# Car_Driver.net
KiCad netlist of a schematic drawn in Altium Designer
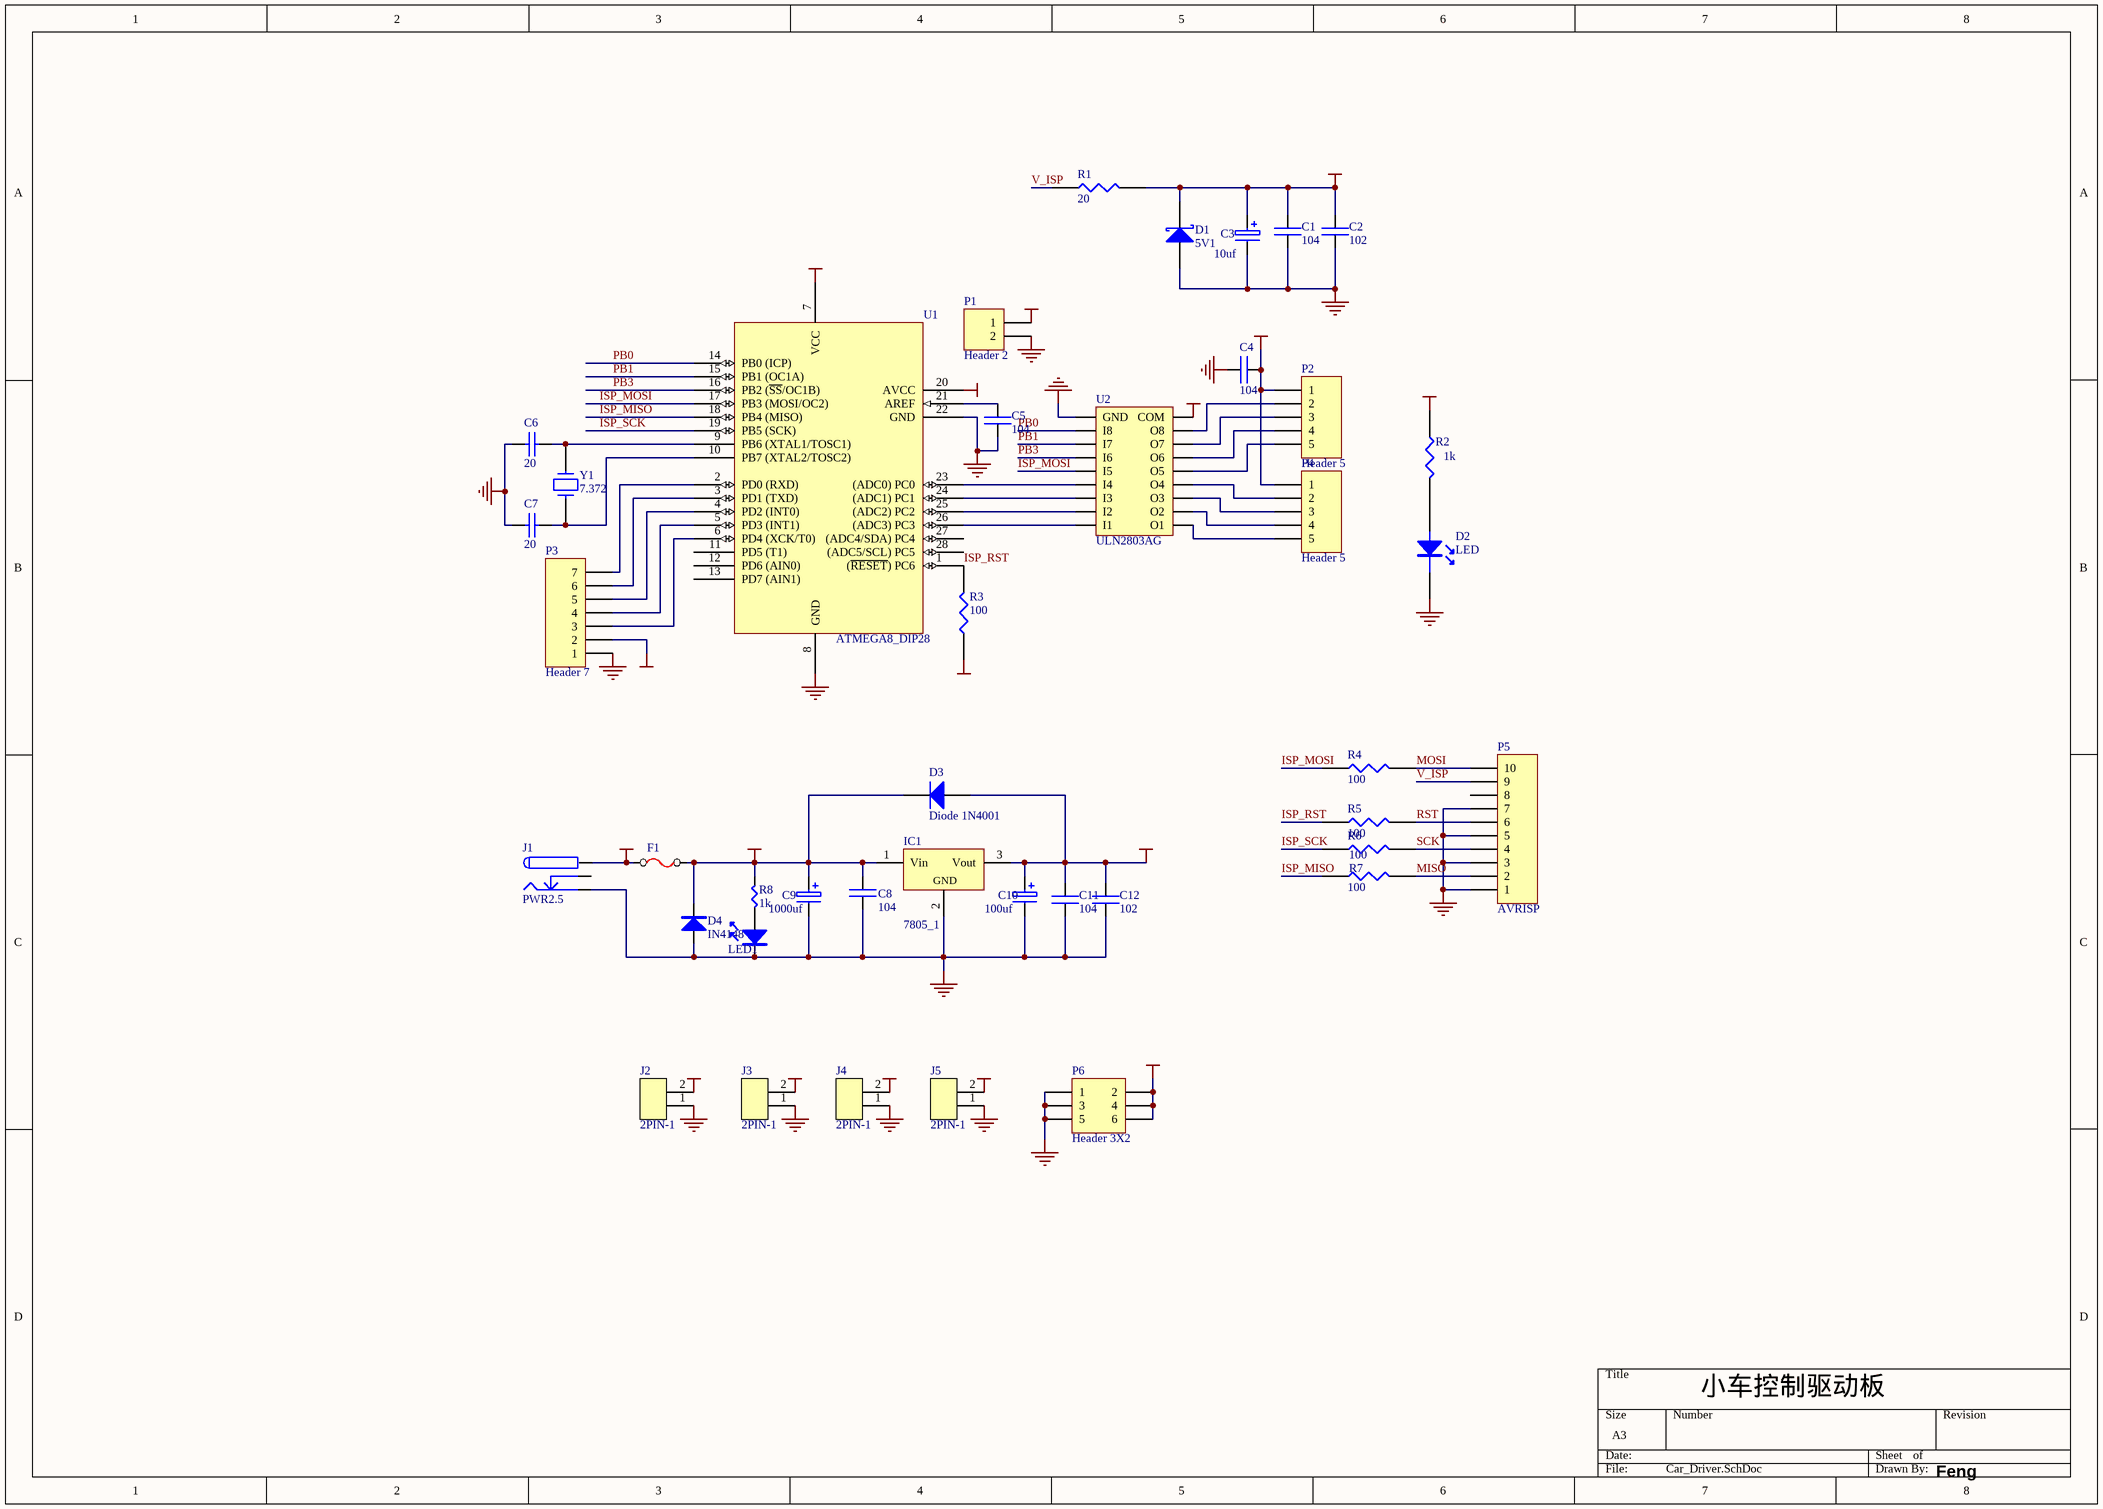
[diagram p0: Car_Driver.SchDoc]

(export (version "E")
  (design (tool "Eeschema 10.0.6"))
  (components
    (comp (ref "C1") (value "104") (footprint "CB1") (libsource (lib "Traffic_light") (part "E_4")))
    (comp (ref "C2") (value "102") (footprint "CB1") (libsource (lib "Traffic_light") (part "E_4")))
    (comp (ref "C3") (value "10uf") (footprint "10U16") (libsource (lib "Traffic_light") (part "E_2")))
    (comp (ref "C4") (value "104") (footprint "CB1") (libsource (lib "Traffic_light") (part "E_4")))
    (comp (ref "C5") (value "104") (footprint "CB1") (libsource (lib "Traffic_light") (part "E_4")))
    (comp (ref "C6")
      (value "20")
      (footprint "CB1")
      (description "Capacitor")
      (libsource (lib "*") (part "CAP"))
    )
    (comp (ref "C7")
      (value "20")
      (footprint "CB1")
      (description "Capacitor")
      (libsource (lib "*") (part "CAP"))
    )
    (comp (ref "C8") (value "104") (footprint "cap_104") (libsource (lib "*") (part "E_4")))
    (comp (ref "C9") (value "1000uf") (footprint "470U25") (libsource (lib "*") (part "E_2")))
    (comp (ref "C10") (value "100uf") (footprint "470U25") (libsource (lib "*") (part "E_2")))
    (comp (ref "C11") (value "104") (footprint "cap_104") (libsource (lib "*") (part "E_4")))
    (comp (ref "C12") (value "102") (footprint "C0.1/0.2") (libsource (lib "*") (part "E_4")))
    (comp (ref "D1")
      (value "5V1")
      (footprint "DIODE")
      (description "Schottky Diode")
      (fields (field (name "PUBLISHER") "Altium Limited"))
      (libsource (lib "Miscellaneous Devices") (part "D Schottky"))
    )
    (comp (ref "D2") (value "LED") (footprint "LED_5") (libsource (lib "*") (part "LED")))
    (comp (ref "D3")
      (value "Diode 1N4001")
      (footprint "diode")
      (description "1 Amp General Purpose Rectifier")
      (fields (field (name "PUBLISHER") "Altium Limited"))
      (libsource (lib "Miscellaneous Devices") (part "Diode 1N4001"))
    )
    (comp (ref "D4") (value "IN4148") (footprint "DIODE") (libsource (lib "晶体管") (part "IN4148")))
    (comp (ref "F1")
      (value "FUSE")
      (footprint "CAP_104")
      (description "Fuse")
      (libsource (lib "模拟器件") (part "FUSE"))
    )
    (comp (ref "IC1") (value "7805_1") (footprint "to-220") (libsource (lib "*") (part "7805_1")))
    (comp (ref "J1")
      (value "PWR2.5")
      (footprint "DC3")
      (description "Low Voltage Power Supply Connector")
      (fields (field (name "PUBLISHER") "Altium Limited"))
      (libsource (lib "Traffic_light") (part "PWR2.5"))
    )
    (comp (ref "J2") (value "2PIN-1") (footprint "HDR1X2H") (libsource (lib "接插件") (part "2PIN-1")))
    (comp (ref "J3") (value "2PIN-1") (footprint "HDR1X2H") (libsource (lib "接插件") (part "2PIN-1")))
    (comp (ref "J4") (value "2PIN-1") (footprint "HDR1X2H") (libsource (lib "接插件") (part "2PIN-1")))
    (comp (ref "J5") (value "2PIN-1") (footprint "HDR1X2H") (libsource (lib "接插件") (part "2PIN-1")))
    (comp (ref "LED1") (value "*") (footprint "LED_5") (libsource (lib "Traffic_light") (part "LED_1")))
    (comp (ref "P1")
      (value "Header 2")
      (footprint "HDR1X2")
      (description "Header, 2-Pin")
      (fields (field (name "PUBLISHER") "Altium Limited"))
      (libsource (lib "Miscellaneous Connectors") (part "Header 2"))
    )
    (comp (ref "P2")
      (value "Header 5")
      (footprint "HDR1X5")
      (description "Header, 5-Pin")
      (fields (field (name "PUBLISHER") "Altium Limited"))
      (libsource (lib "Miscellaneous Connectors") (part "Header 5"))
    )
    (comp (ref "P3")
      (value "Header 7")
      (footprint "HDR1X7H")
      (description "Header, 7-Pin")
      (fields (field (name "PUBLISHER") "Altium Limited"))
      (libsource (lib "Miscellaneous Connectors") (part "Header 7"))
    )
    (comp (ref "P4")
      (value "Header 5")
      (footprint "HDR1X5")
      (description "Header, 5-Pin")
      (fields (field (name "PUBLISHER") "Altium Limited"))
      (libsource (lib "Miscellaneous Connectors") (part "Header 5"))
    )
    (comp (ref "P5")
      (value "AVRISP")
      (footprint "ISP")
      (description "Connector")
      (libsource (lib "*") (part "CON10"))
    )
    (comp (ref "P6")
      (value "Header 3X2")
      (footprint "HDR2X3")
      (description "Header, 3-Pin, Dual row")
      (fields (field (name "PUBLISHER") "Altium Limited"))
      (libsource (lib "Miscellaneous Connectors") (part "Header 3X2"))
    )
    (comp (ref "R1") (value "20") (footprint "AXIAL0.4") (libsource (lib "*") (part "RES1")))
    (comp (ref "R2") (value "1k") (footprint "AXIAL0.4") (libsource (lib "*") (part "RES1")))
    (comp (ref "R3") (value "100") (footprint "AXIAL0.4") (libsource (lib "*") (part "RES1")))
    (comp (ref "R4") (value "100") (footprint "AXIAL0.4") (libsource (lib "*") (part "RES1")))
    (comp (ref "R5") (value "100") (footprint "AXIAL0.4") (libsource (lib "*") (part "RES1")))
    (comp (ref "R6") (value "100") (footprint "AXIAL0.4") (libsource (lib "*") (part "RES1")))
    (comp (ref "R7") (value "100") (footprint "AXIAL0.4") (libsource (lib "*") (part "RES1")))
    (comp (ref "R8") (value "1k") (footprint "AXIAL0.4") (libsource (lib "Traffic_light") (part "R1")))
    (comp (ref "U1")
      (value "ATMEGA8_DIP28")
      (footprint "28P3")
      (description "Atmel Microcontroller - Library created by carel..  <www.mpfreezone.com>")
      (libsource (lib "*") (part "ATMEGA8_DIP28"))
    )
    (comp (ref "U2")
      (value "ULN2803AG")
      (footprint "DIP18")
      (libsource (lib "Traffic_light") (part "TD62081"))
    )
    (comp (ref "Y1")
      (value "7.372")
      (footprint "XTAL_US")
      (description "Crystal")
      (libsource (lib "*") (part "CRYSTAL"))
    )
  )
  (nets
    (net (code "1") (name "/ISP_MISO") (class "Default")
      (node (ref "R7") (pin "1") (pinfunction "1_1") (pintype "passive"))
      (node (ref "U1") (pin "18") (pinfunction "PB4_(MISO)_18") (pintype "bidirectional"))
    )
    (net (code "2") (name "/ISP_MOSI") (class "Default")
      (node (ref "R4") (pin "1") (pinfunction "1_1") (pintype "passive"))
      (node (ref "U1") (pin "17") (pinfunction "PB3_(MOSI/OC2)_17") (pintype "bidirectional"))
      (node (ref "U2") (pin "5") (pinfunction "I5_5") (pintype "passive"))
    )
    (net (code "3") (name "/ISP_RST") (class "Default")
      (node (ref "R3") (pin "2") (pinfunction "2_2") (pintype "passive"))
      (node (ref "R5") (pin "1") (pinfunction "1_1") (pintype "passive"))
      (node (ref "U1") (pin "1") (pinfunction "(~{RESET})_PC6_1") (pintype "bidirectional"))
    )
    (net (code "4") (name "/ISP_SCK") (class "Default")
      (node (ref "R6") (pin "1") (pinfunction "1_1") (pintype "passive"))
      (node (ref "U1") (pin "19") (pinfunction "PB5_(SCK)_19") (pintype "bidirectional"))
    )
    (net (code "5") (name "/MISO") (class "Default")
      (node (ref "P5") (pin "2") (pinfunction "2_2") (pintype "passive"))
      (node (ref "R7") (pin "2") (pinfunction "2_2") (pintype "passive"))
    )
    (net (code "6") (name "/MOSI") (class "Default")
      (node (ref "P5") (pin "10") (pinfunction "10_10") (pintype "passive"))
      (node (ref "R4") (pin "2") (pinfunction "2_2") (pintype "passive"))
    )
    (net (code "7") (name "/PB0") (class "Default")
      (node (ref "U1") (pin "14") (pinfunction "PB0_(ICP)_14") (pintype "bidirectional"))
      (node (ref "U2") (pin "8") (pinfunction "I8_8") (pintype "passive"))
    )
    (net (code "8") (name "/PB1") (class "Default")
      (node (ref "U1") (pin "15") (pinfunction "PB1_(OC1A)_15") (pintype "bidirectional"))
      (node (ref "U2") (pin "7") (pinfunction "I7_7") (pintype "passive"))
    )
    (net (code "9") (name "/PB3") (class "Default")
      (node (ref "U1") (pin "16") (pinfunction "PB2_(~{SS}/OC1B)_16") (pintype "bidirectional"))
      (node (ref "U2") (pin "6") (pinfunction "I6_6") (pintype "passive"))
    )
    (net (code "10") (name "/RST") (class "Default")
      (node (ref "P5") (pin "6") (pinfunction "6_6") (pintype "passive"))
      (node (ref "R5") (pin "2") (pinfunction "2_2") (pintype "passive"))
    )
    (net (code "11") (name "/SCK") (class "Default")
      (node (ref "P5") (pin "4") (pinfunction "4_4") (pintype "passive"))
      (node (ref "R6") (pin "2") (pinfunction "2_2") (pintype "passive"))
    )
    (net (code "12") (name "/V_ISP") (class "Default")
      (node (ref "P5") (pin "9") (pinfunction "9_9") (pintype "passive"))
      (node (ref "R1") (pin "1") (pinfunction "1_1") (pintype "passive"))
    )
    (net (code "13") (name "GND") (class "Default")
      (node (ref "C1") (pin "2") (pintype "passive"))
      (node (ref "C10") (pin "2") (pintype "passive"))
      (node (ref "C11") (pin "2") (pintype "passive"))
      (node (ref "C12") (pin "2") (pintype "passive"))
      (node (ref "C2") (pin "2") (pintype "passive"))
      (node (ref "C3") (pin "2") (pintype "passive"))
      (node (ref "C4") (pin "1") (pintype "passive"))
      (node (ref "C5") (pin "2") (pintype "passive"))
      (node (ref "C6") (pin "1") (pinfunction "1_1") (pintype "passive"))
      (node (ref "C7") (pin "1") (pinfunction "1_1") (pintype "passive"))
      (node (ref "C8") (pin "2") (pintype "passive"))
      (node (ref "C9") (pin "2") (pintype "passive"))
      (node (ref "D1") (pin "1") (pinfunction "A_1") (pintype "passive"))
      (node (ref "D2") (pin "2") (pinfunction "2_2") (pintype "passive"))
      (node (ref "D4") (pin "1") (pintype "passive"))
      (node (ref "IC1") (pin "2") (pinfunction "GND_2") (pintype "passive"))
      (node (ref "J1") (pin "2") (pinfunction "2_2") (pintype "power_in"))
      (node (ref "J2") (pin "1") (pintype "passive"))
      (node (ref "J3") (pin "1") (pintype "passive"))
      (node (ref "J4") (pin "1") (pintype "passive"))
      (node (ref "J5") (pin "1") (pintype "passive"))
      (node (ref "LED1") (pin "2") (pintype "passive"))
      (node (ref "P1") (pin "2") (pinfunction "2_2") (pintype "passive"))
      (node (ref "P3") (pin "1") (pinfunction "1_1") (pintype "passive"))
      (node (ref "P5") (pin "1") (pinfunction "1_1") (pintype "passive"))
      (node (ref "P5") (pin "3") (pinfunction "3_3") (pintype "passive"))
      (node (ref "P5") (pin "5") (pinfunction "5_5") (pintype "passive"))
      (node (ref "P5") (pin "7") (pinfunction "7_7") (pintype "passive"))
      (node (ref "P6") (pin "1") (pinfunction "1_1") (pintype "passive"))
      (node (ref "P6") (pin "3") (pinfunction "3_3") (pintype "passive"))
      (node (ref "P6") (pin "5") (pinfunction "5_5") (pintype "passive"))
      (node (ref "U1") (pin "22") (pinfunction "GND_22") (pintype "passive"))
      (node (ref "U1") (pin "8") (pinfunction "GND_8") (pintype "passive"))
      (node (ref "U2") (pin "9") (pinfunction "GND_9") (pintype "passive"))
    )
    (net (code "14") (name "Net-(D2-Pad1)") (class "Default")
      (node (ref "D2") (pin "1") (pinfunction "1_1") (pintype "passive"))
      (node (ref "R2") (pin "2") (pinfunction "2_2") (pintype "passive"))
    )
    (net (code "15") (name "Net-(LED1-Pad1)") (class "Default")
      (node (ref "LED1") (pin "1") (pintype "passive"))
      (node (ref "R8") (pin "1") (pintype "passive"))
    )
    (net (code "16") (name "Net-(U1-(ADC0)_PC0)") (class "Default")
      (node (ref "U1") (pin "23") (pinfunction "(ADC0)_PC0_23") (pintype "bidirectional"))
      (node (ref "U2") (pin "4") (pinfunction "I4_4") (pintype "passive"))
    )
    (net (code "17") (name "Net-(U1-(ADC1)_PC1)") (class "Default")
      (node (ref "U1") (pin "24") (pinfunction "(ADC1)_PC1_24") (pintype "bidirectional"))
      (node (ref "U2") (pin "3") (pinfunction "I3_3") (pintype "passive"))
    )
    (net (code "18") (name "Net-(U1-(ADC2)_PC2)") (class "Default")
      (node (ref "U1") (pin "25") (pinfunction "(ADC2)_PC2_25") (pintype "bidirectional"))
      (node (ref "U2") (pin "2") (pinfunction "I2_2") (pintype "passive"))
    )
    (net (code "19") (name "Net-(U1-(ADC3)_PC3)") (class "Default")
      (node (ref "U1") (pin "26") (pinfunction "(ADC3)_PC3_26") (pintype "bidirectional"))
      (node (ref "U2") (pin "1") (pinfunction "I1_1") (pintype "passive"))
    )
    (net (code "20") (name "Net-(U1-AREF)") (class "Default")
      (node (ref "C5") (pin "1") (pintype "passive"))
      (node (ref "U1") (pin "21") (pinfunction "AREF_21") (pintype "input"))
    )
    (net (code "21") (name "Net-(U1-PB6_(XTAL1{slash}TOSC1))") (class "Default")
      (node (ref "C6") (pin "2") (pinfunction "2_2") (pintype "passive"))
      (node (ref "U1") (pin "9") (pinfunction "PB6_(XTAL1/TOSC1)_9") (pintype "passive"))
      (node (ref "Y1") (pin "1") (pinfunction "1_1") (pintype "passive"))
    )
    (net (code "22") (name "Net-(U1-PB7_(XTAL2{slash}TOSC2))") (class "Default")
      (node (ref "C7") (pin "2") (pinfunction "2_2") (pintype "passive"))
      (node (ref "U1") (pin "10") (pinfunction "PB7_(XTAL2/TOSC2)_10") (pintype "passive"))
      (node (ref "Y1") (pin "2") (pinfunction "2_2") (pintype "passive"))
    )
    (net (code "23") (name "Net-(U1-PD0_(RXD))") (class "Default")
      (node (ref "P3") (pin "7") (pinfunction "7_7") (pintype "passive"))
      (node (ref "U1") (pin "2") (pinfunction "PD0_(RXD)_2") (pintype "bidirectional"))
    )
    (net (code "24") (name "Net-(U1-PD1_(TXD))") (class "Default")
      (node (ref "P3") (pin "6") (pinfunction "6_6") (pintype "passive"))
      (node (ref "U1") (pin "3") (pinfunction "PD1_(TXD)_3") (pintype "bidirectional"))
    )
    (net (code "25") (name "Net-(U1-PD2_(INT0))") (class "Default")
      (node (ref "P3") (pin "5") (pinfunction "5_5") (pintype "passive"))
      (node (ref "U1") (pin "4") (pinfunction "PD2_(INT0)_4") (pintype "bidirectional"))
    )
    (net (code "26") (name "Net-(U1-PD3_(INT1))") (class "Default")
      (node (ref "P3") (pin "4") (pinfunction "4_4") (pintype "passive"))
      (node (ref "U1") (pin "5") (pinfunction "PD3_(INT1)_5") (pintype "bidirectional"))
    )
    (net (code "27") (name "Net-(U1-PD4_(XCK{slash}T0))") (class "Default")
      (node (ref "P3") (pin "3") (pinfunction "3_3") (pintype "passive"))
      (node (ref "U1") (pin "6") (pinfunction "PD4_(XCK/T0)_6") (pintype "bidirectional"))
    )
    (net (code "28") (name "Net-(U2-O1)") (class "Default")
      (node (ref "P4") (pin "5") (pinfunction "5_5") (pintype "passive"))
      (node (ref "U2") (pin "18") (pinfunction "O1_18") (pintype "passive"))
    )
    (net (code "29") (name "Net-(U2-O2)") (class "Default")
      (node (ref "P4") (pin "4") (pinfunction "4_4") (pintype "passive"))
      (node (ref "U2") (pin "17") (pinfunction "O2_17") (pintype "passive"))
    )
    (net (code "30") (name "Net-(U2-O3)") (class "Default")
      (node (ref "P4") (pin "3") (pinfunction "3_3") (pintype "passive"))
      (node (ref "U2") (pin "16") (pinfunction "O3_16") (pintype "passive"))
    )
    (net (code "31") (name "Net-(U2-O4)") (class "Default")
      (node (ref "P4") (pin "2") (pinfunction "2_2") (pintype "passive"))
      (node (ref "U2") (pin "15") (pinfunction "O4_15") (pintype "passive"))
    )
    (net (code "32") (name "Net-(U2-O5)") (class "Default")
      (node (ref "P2") (pin "5") (pinfunction "5_5") (pintype "passive"))
      (node (ref "U2") (pin "14") (pinfunction "O5_14") (pintype "passive"))
    )
    (net (code "33") (name "Net-(U2-O6)") (class "Default")
      (node (ref "P2") (pin "4") (pinfunction "4_4") (pintype "passive"))
      (node (ref "U2") (pin "13") (pinfunction "O6_13") (pintype "passive"))
    )
    (net (code "34") (name "Net-(U2-O7)") (class "Default")
      (node (ref "P2") (pin "3") (pinfunction "3_3") (pintype "passive"))
      (node (ref "U2") (pin "12") (pinfunction "O7_12") (pintype "passive"))
    )
    (net (code "35") (name "Net-(U2-O8)") (class "Default")
      (node (ref "P2") (pin "2") (pinfunction "2_2") (pintype "passive"))
      (node (ref "U2") (pin "11") (pinfunction "O8_11") (pintype "passive"))
    )
    (net (code "36") (name "VCC") (class "Default")
      (node (ref "C1") (pin "1") (pintype "passive"))
      (node (ref "C10") (pin "1") (pintype "passive"))
      (node (ref "C11") (pin "1") (pintype "passive"))
      (node (ref "C12") (pin "1") (pintype "passive"))
      (node (ref "C2") (pin "1") (pintype "passive"))
      (node (ref "C3") (pin "1") (pintype "passive"))
      (node (ref "D1") (pin "2") (pinfunction "K_2") (pintype "passive"))
      (node (ref "D3") (pin "1") (pinfunction "A_1") (pintype "passive"))
      (node (ref "IC1") (pin "3") (pinfunction "Vout_3") (pintype "passive"))
      (node (ref "P3") (pin "2") (pinfunction "2_2") (pintype "passive"))
      (node (ref "P6") (pin "2") (pinfunction "2_2") (pintype "passive"))
      (node (ref "P6") (pin "4") (pinfunction "4_4") (pintype "passive"))
      (node (ref "P6") (pin "6") (pinfunction "6_6") (pintype "passive"))
      (node (ref "R1") (pin "2") (pinfunction "2_2") (pintype "passive"))
      (node (ref "R2") (pin "1") (pinfunction "1_1") (pintype "passive"))
      (node (ref "R3") (pin "1") (pinfunction "1_1") (pintype "passive"))
      (node (ref "U1") (pin "20") (pinfunction "AVCC_20") (pintype "passive"))
      (node (ref "U1") (pin "7") (pinfunction "VCC_7") (pintype "passive"))
    )
    (net (code "37") (name "V_S") (class "Default")
      (node (ref "F1") (pin "1") (pinfunction "1_1") (pintype "passive"))
      (node (ref "J1") (pin "1") (pinfunction "1_1") (pintype "power_in"))
      (node (ref "J2") (pin "2") (pintype "passive"))
      (node (ref "J3") (pin "2") (pintype "passive"))
    )
    (net (code "38") (name "Vin") (class "Default")
      (node (ref "C4") (pin "2") (pintype "passive"))
      (node (ref "C8") (pin "1") (pintype "passive"))
      (node (ref "C9") (pin "1") (pintype "passive"))
      (node (ref "D3") (pin "2") (pinfunction "K_2") (pintype "passive"))
      (node (ref "D4") (pin "2") (pintype "passive"))
      (node (ref "F1") (pin "2") (pinfunction "2_2") (pintype "passive"))
      (node (ref "IC1") (pin "1") (pinfunction "Vin_1") (pintype "passive"))
      (node (ref "J4") (pin "2") (pintype "passive"))
      (node (ref "J5") (pin "2") (pintype "passive"))
      (node (ref "P1") (pin "1") (pinfunction "1_1") (pintype "passive"))
      (node (ref "P2") (pin "1") (pinfunction "1_1") (pintype "passive"))
      (node (ref "P4") (pin "1") (pinfunction "1_1") (pintype "passive"))
      (node (ref "R8") (pin "2") (pintype "passive"))
      (node (ref "U2") (pin "10") (pinfunction "COM_10") (pintype "passive"))
    )
    (net (code "39") (name "unconnected-(J1-Pad3)") (class "Default")
      (node (ref "J1") (pin "3") (pinfunction "3_3") (pintype "power_in"))
    )
    (net (code "40") (name "unconnected-(P5-Pad8)") (class "Default")
      (node (ref "P5") (pin "8") (pinfunction "8_8") (pintype "passive"))
    )
    (net (code "41") (name "unconnected-(U1-(ADC4{slash}SDA)_PC4-Pad27)") (class "Default")
      (node (ref "U1") (pin "27") (pinfunction "(ADC4/SDA)_PC4_27") (pintype "bidirectional"))
    )
    (net (code "42") (name "unconnected-(U1-(ADC5{slash}SCL)_PC5-Pad28)") (class "Default")
      (node (ref "U1") (pin "28") (pinfunction "(ADC5/SCL)_PC5_28") (pintype "bidirectional"))
    )
    (net (code "43") (name "unconnected-(U1-PD5_(T1)-Pad11)") (class "Default")
      (node (ref "U1") (pin "11") (pinfunction "PD5_(T1)_11") (pintype "passive"))
    )
    (net (code "44") (name "unconnected-(U1-PD6_(AIN0)-Pad12)") (class "Default")
      (node (ref "U1") (pin "12") (pinfunction "PD6_(AIN0)_12") (pintype "passive"))
    )
    (net (code "45") (name "unconnected-(U1-PD7_(AIN1)-Pad13)") (class "Default")
      (node (ref "U1") (pin "13") (pinfunction "PD7_(AIN1)_13") (pintype "passive"))
    )
  )
)
